# mini.net
KiCad netlist of a schematic drawn in EAGLE
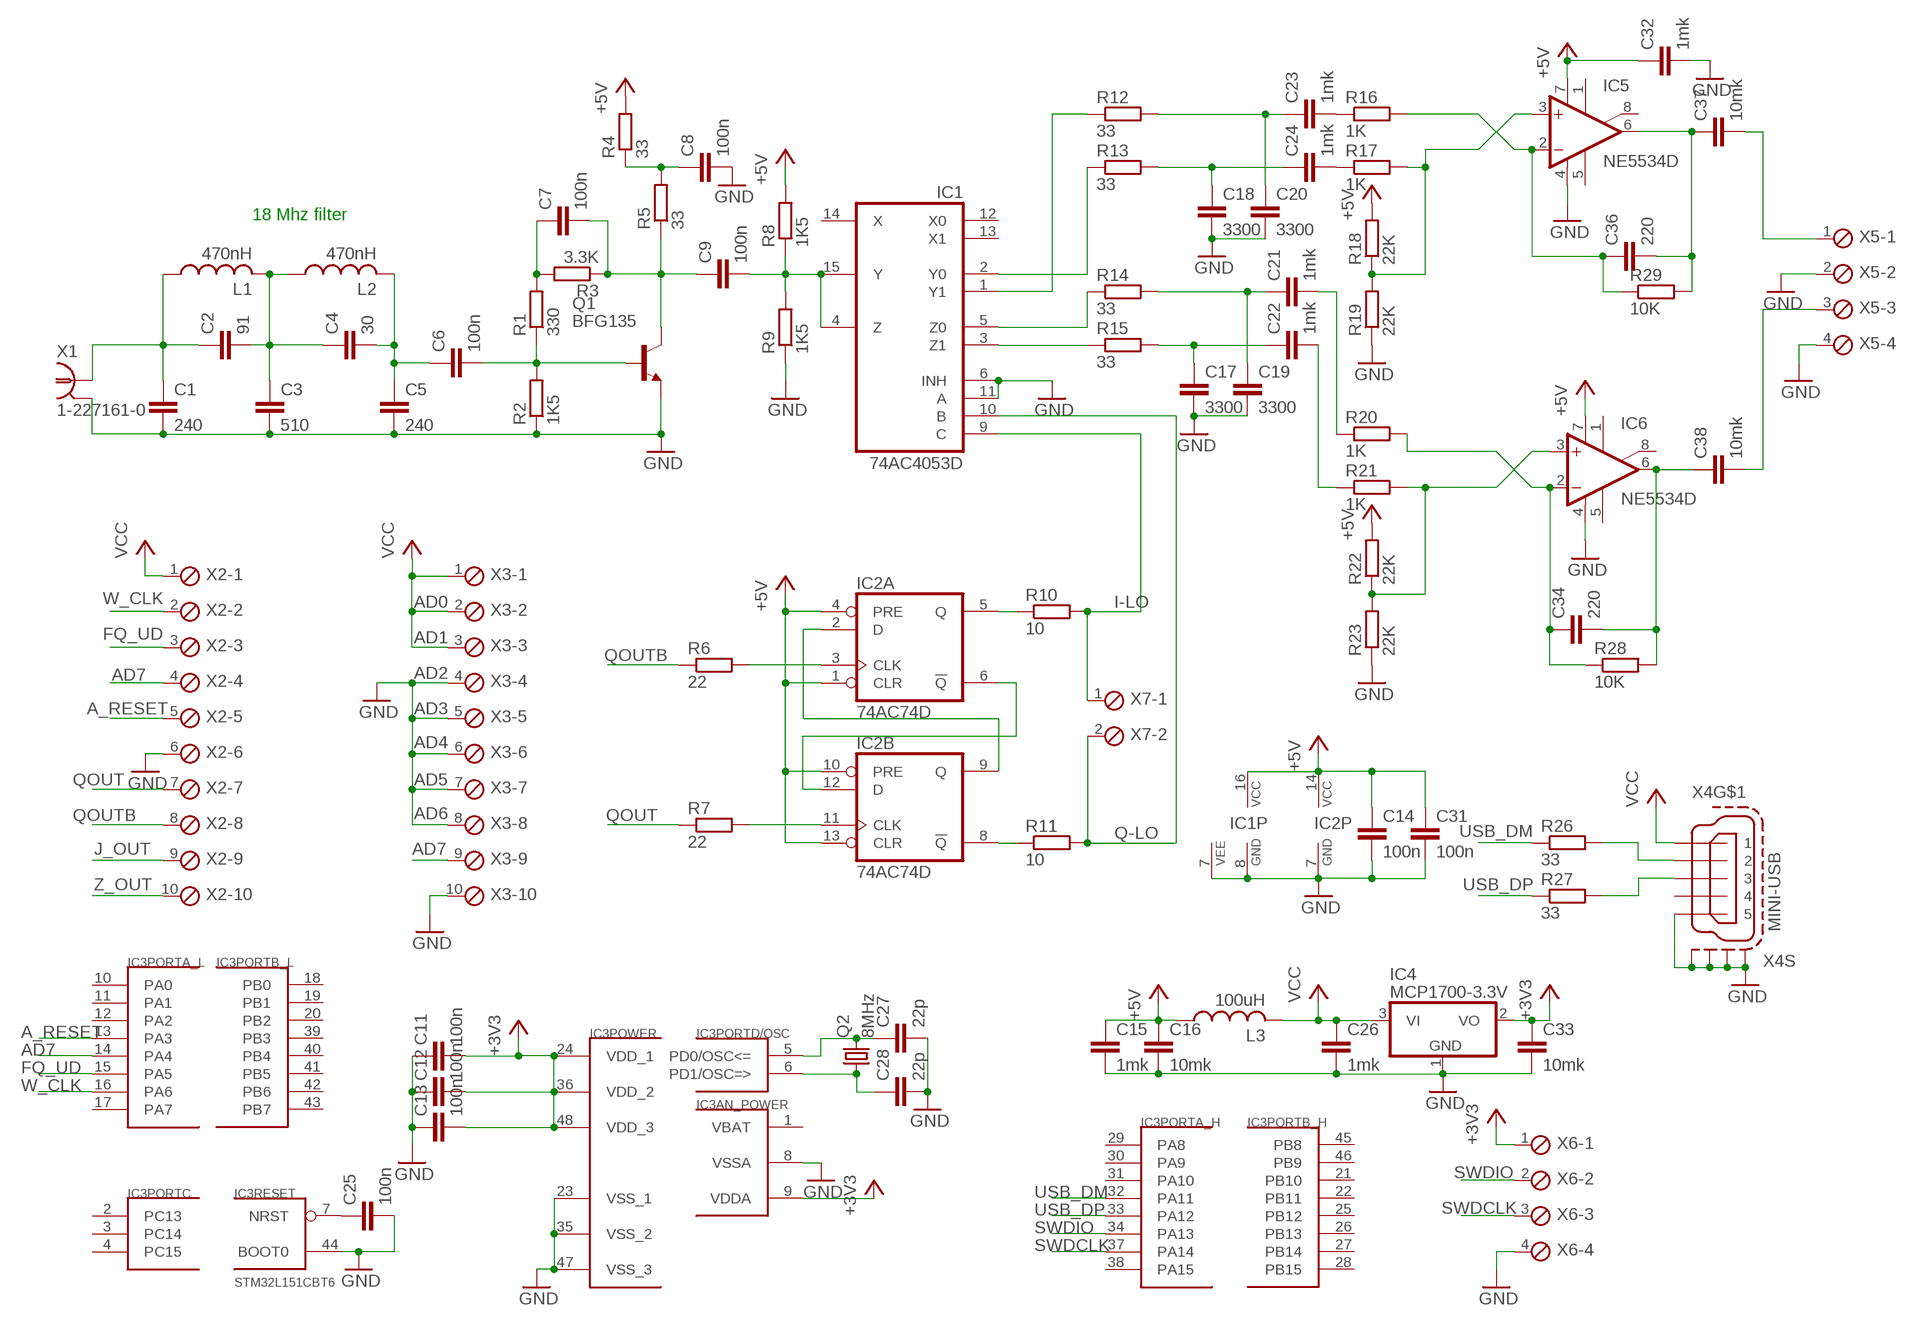
[diagram p0: schematic, sheet 1]

(export (version "E")
  (design (tool "Eeschema 10.0.6"))
  (components
    (comp (ref "C1")
      (value "240")
      (footprint "eagle-import:C0805")
      (libsource (lib "eagle-import") (part "C-EUC0805"))
    )
    (comp (ref "C2")
      (value "91")
      (footprint "eagle-import:C0805")
      (libsource (lib "eagle-import") (part "C-EUC0805"))
    )
    (comp (ref "C3")
      (value "510")
      (footprint "eagle-import:C0805")
      (libsource (lib "eagle-import") (part "C-EUC0805"))
    )
    (comp (ref "C4")
      (value "30")
      (footprint "eagle-import:C0805")
      (libsource (lib "eagle-import") (part "C-EUC0805"))
    )
    (comp (ref "C5")
      (value "240")
      (footprint "eagle-import:C0805")
      (libsource (lib "eagle-import") (part "C-EUC0805"))
    )
    (comp (ref "C6")
      (value "100n")
      (footprint "eagle-import:C0603")
      (libsource (lib "eagle-import") (part "C-EUC0603"))
    )
    (comp (ref "C7")
      (value "100n")
      (footprint "eagle-import:C0603")
      (libsource (lib "eagle-import") (part "C-EUC0603"))
    )
    (comp (ref "C8")
      (value "100n")
      (footprint "eagle-import:C0603")
      (libsource (lib "eagle-import") (part "C-EUC0603"))
    )
    (comp (ref "C9")
      (value "100n")
      (footprint "eagle-import:C0603")
      (libsource (lib "eagle-import") (part "C-EUC0603"))
    )
    (comp (ref "C11")
      (value "100n")
      (footprint "eagle-import:C0603")
      (libsource (lib "eagle-import") (part "C-EUC0603"))
    )
    (comp (ref "C12")
      (value "100n")
      (footprint "eagle-import:C0603")
      (libsource (lib "eagle-import") (part "C-EUC0603"))
    )
    (comp (ref "C13")
      (value "100n")
      (footprint "eagle-import:C0603")
      (libsource (lib "eagle-import") (part "C-EUC0603"))
    )
    (comp (ref "C14")
      (value "100n")
      (footprint "eagle-import:C0603")
      (libsource (lib "eagle-import") (part "C-EUC0603"))
    )
    (comp (ref "C15")
      (value "1mk")
      (footprint "eagle-import:C0603")
      (libsource (lib "eagle-import") (part "C-EUC0603"))
    )
    (comp (ref "C16")
      (value "10mk")
      (footprint "eagle-import:C0805")
      (libsource (lib "eagle-import") (part "C-EUC0805"))
    )
    (comp (ref "C17")
      (value "3300")
      (footprint "eagle-import:C0805")
      (libsource (lib "eagle-import") (part "C-EUC0805"))
    )
    (comp (ref "C18")
      (value "3300")
      (footprint "eagle-import:C0805")
      (libsource (lib "eagle-import") (part "C-EUC0805"))
    )
    (comp (ref "C19")
      (value "3300")
      (footprint "eagle-import:C0805")
      (libsource (lib "eagle-import") (part "C-EUC0805"))
    )
    (comp (ref "C20")
      (value "3300")
      (footprint "eagle-import:C0805")
      (libsource (lib "eagle-import") (part "C-EUC0805"))
    )
    (comp (ref "C21")
      (value "1mk")
      (footprint "eagle-import:C0603")
      (libsource (lib "eagle-import") (part "C-EUC0603"))
    )
    (comp (ref "C22")
      (value "1mk")
      (footprint "eagle-import:C0603")
      (libsource (lib "eagle-import") (part "C-EUC0603"))
    )
    (comp (ref "C23")
      (value "1mk")
      (footprint "eagle-import:C0603")
      (libsource (lib "eagle-import") (part "C-EUC0603"))
    )
    (comp (ref "C24")
      (value "1mk")
      (footprint "eagle-import:C0603")
      (libsource (lib "eagle-import") (part "C-EUC0603"))
    )
    (comp (ref "C25")
      (value "100n")
      (footprint "eagle-import:C0603")
      (libsource (lib "eagle-import") (part "C-EUC0603"))
    )
    (comp (ref "C26")
      (value "1mk")
      (footprint "eagle-import:C0603")
      (libsource (lib "eagle-import") (part "C-EUC0603"))
    )
    (comp (ref "C27")
      (value "22p")
      (footprint "eagle-import:C0603")
      (libsource (lib "eagle-import") (part "C-EUC0603"))
    )
    (comp (ref "C28")
      (value "22p")
      (footprint "eagle-import:C0603")
      (libsource (lib "eagle-import") (part "C-EUC0603"))
    )
    (comp (ref "C31")
      (value "100n")
      (footprint "eagle-import:C0603")
      (libsource (lib "eagle-import") (part "C-EUC0603"))
    )
    (comp (ref "C32")
      (value "1mk")
      (footprint "eagle-import:C0603")
      (libsource (lib "eagle-import") (part "C-EUC0603"))
    )
    (comp (ref "C33")
      (value "10mk")
      (footprint "eagle-import:C0805")
      (libsource (lib "eagle-import") (part "C-EUC0805"))
    )
    (comp (ref "C34")
      (value "220")
      (footprint "eagle-import:C0805")
      (libsource (lib "eagle-import") (part "C-EUC0805"))
    )
    (comp (ref "C36")
      (value "220")
      (footprint "eagle-import:C0805")
      (libsource (lib "eagle-import") (part "C-EUC0805"))
    )
    (comp (ref "C37")
      (value "10mk")
      (footprint "eagle-import:C0805")
      (libsource (lib "eagle-import") (part "C-EUC0805"))
    )
    (comp (ref "C38")
      (value "10mk")
      (footprint "eagle-import:C0805")
      (libsource (lib "eagle-import") (part "C-EUC0805"))
    )
    (comp (ref "IC1")
      (value "74AC4053D")
      (footprint "eagle-import:SO16")
      (libsource (lib "eagle-import") (part "4053D"))
    )
    (comp (ref "IC2")
      (value "74AC74D")
      (footprint "eagle-import:SO14")
      (libsource (lib "eagle-import") (part "7474DAC"))
    )
    (comp (ref "IC3")
      (value "STM32L151CBT6")
      (footprint "eagle-import:TQFP48")
      (libsource (lib "eagle-import") (part "STM32F10XCXT6"))
    )
    (comp (ref "IC4")
      (value "MCP1700-3.3V")
      (footprint "eagle-import:SOT23")
      (libsource (lib "eagle-import") (part "MCP1703CB"))
    )
    (comp (ref "IC5")
      (value "NE5534D")
      (footprint "eagle-import:SO08")
      (libsource (lib "eagle-import") (part "NE5534D"))
    )
    (comp (ref "IC6")
      (value "NE5534D")
      (footprint "eagle-import:SO08")
      (libsource (lib "eagle-import") (part "NE5534D"))
    )
    (comp (ref "L1")
      (value "470nH")
      (footprint "eagle-import:L3225M")
      (libsource (lib "eagle-import") (part "L-USL3225M"))
    )
    (comp (ref "L2")
      (value "470nH")
      (footprint "eagle-import:L3225M")
      (libsource (lib "eagle-import") (part "L-USL3225M"))
    )
    (comp (ref "L3")
      (value "100uH")
      (footprint "eagle-import:0207_12")
      (libsource (lib "eagle-import") (part "L-US0207/12"))
    )
    (comp (ref "Q1")
      (value "BFG135")
      (footprint "eagle-import:SOT223")
      (libsource (lib "eagle-import") (part "BFG135"))
    )
    (comp (ref "Q2")
      (value "8MHz")
      (footprint "eagle-import:HC49_S")
      (libsource (lib "eagle-import") (part "CRYSTALHC49S"))
    )
    (comp (ref "R1")
      (value "330")
      (footprint "eagle-import:R0603")
      (libsource (lib "eagle-import") (part "R-EU_R0603"))
    )
    (comp (ref "R2")
      (value "1K5")
      (footprint "eagle-import:R0603")
      (libsource (lib "eagle-import") (part "R-EU_R0603"))
    )
    (comp (ref "R3")
      (value "3.3K")
      (footprint "eagle-import:R0603")
      (libsource (lib "eagle-import") (part "R-EU_R0603"))
    )
    (comp (ref "R4")
      (value "33")
      (footprint "eagle-import:R0603")
      (libsource (lib "eagle-import") (part "R-EU_R0603"))
    )
    (comp (ref "R5")
      (value "33")
      (footprint "eagle-import:R0603")
      (libsource (lib "eagle-import") (part "R-EU_R0603"))
    )
    (comp (ref "R6")
      (value "22")
      (footprint "eagle-import:R0603")
      (libsource (lib "eagle-import") (part "R-EU_R0603"))
    )
    (comp (ref "R7")
      (value "22")
      (footprint "eagle-import:R0603")
      (libsource (lib "eagle-import") (part "R-EU_R0603"))
    )
    (comp (ref "R8")
      (value "1K5")
      (footprint "eagle-import:R0603")
      (libsource (lib "eagle-import") (part "R-EU_R0603"))
    )
    (comp (ref "R9")
      (value "1K5")
      (footprint "eagle-import:R0603")
      (libsource (lib "eagle-import") (part "R-EU_R0603"))
    )
    (comp (ref "R10")
      (value "10")
      (footprint "eagle-import:R0603")
      (libsource (lib "eagle-import") (part "R-EU_R0603"))
    )
    (comp (ref "R11")
      (value "10")
      (footprint "eagle-import:R0603")
      (libsource (lib "eagle-import") (part "R-EU_R0603"))
    )
    (comp (ref "R12")
      (value "33")
      (footprint "eagle-import:R0603")
      (libsource (lib "eagle-import") (part "R-EU_R0603"))
    )
    (comp (ref "R13")
      (value "33")
      (footprint "eagle-import:R0603")
      (libsource (lib "eagle-import") (part "R-EU_R0603"))
    )
    (comp (ref "R14")
      (value "33")
      (footprint "eagle-import:R0603")
      (libsource (lib "eagle-import") (part "R-EU_R0603"))
    )
    (comp (ref "R15")
      (value "33")
      (footprint "eagle-import:R0603")
      (libsource (lib "eagle-import") (part "R-EU_R0603"))
    )
    (comp (ref "R16")
      (value "1K")
      (footprint "eagle-import:R0603")
      (libsource (lib "eagle-import") (part "R-EU_R0603"))
    )
    (comp (ref "R17")
      (value "1K")
      (footprint "eagle-import:R0603")
      (libsource (lib "eagle-import") (part "R-EU_R0603"))
    )
    (comp (ref "R18")
      (value "22K")
      (footprint "eagle-import:R0603")
      (libsource (lib "eagle-import") (part "R-EU_R0603"))
    )
    (comp (ref "R19")
      (value "22K")
      (footprint "eagle-import:R0603")
      (libsource (lib "eagle-import") (part "R-EU_R0603"))
    )
    (comp (ref "R20")
      (value "1K")
      (footprint "eagle-import:R0603")
      (libsource (lib "eagle-import") (part "R-EU_R0603"))
    )
    (comp (ref "R21")
      (value "1K")
      (footprint "eagle-import:R0603")
      (libsource (lib "eagle-import") (part "R-EU_R0603"))
    )
    (comp (ref "R22")
      (value "22K")
      (footprint "eagle-import:R0603")
      (libsource (lib "eagle-import") (part "R-EU_R0603"))
    )
    (comp (ref "R23")
      (value "22K")
      (footprint "eagle-import:R0603")
      (libsource (lib "eagle-import") (part "R-EU_R0603"))
    )
    (comp (ref "R26")
      (value "33")
      (footprint "eagle-import:R0603")
      (libsource (lib "eagle-import") (part "R-EU_R0603"))
    )
    (comp (ref "R27")
      (value "33")
      (footprint "eagle-import:R0603")
      (libsource (lib "eagle-import") (part "R-EU_R0603"))
    )
    (comp (ref "R28")
      (value "10K")
      (footprint "eagle-import:R0603")
      (libsource (lib "eagle-import") (part "R-EU_R0603"))
    )
    (comp (ref "R29")
      (value "10K")
      (footprint "eagle-import:R0603")
      (libsource (lib "eagle-import") (part "R-EU_R0603"))
    )
    (comp (ref "X1")
      (value "1-227161-0")
      (footprint "eagle-import:AMP_227161")
      (fields (field (name "MF") "TYCO ELECTRONICS") (field (name "MPN") "1-227161"))
      (libsource (lib "eagle-import") (part "?2271611--0"))
    )
    (comp (ref "X2")
      (value "MPT10")
      (footprint "eagle-import:10POL254")
      (libsource (lib "eagle-import") (part "MPT10"))
    )
    (comp (ref "X3")
      (value "MPT10")
      (footprint "eagle-import:10POL254")
      (libsource (lib "eagle-import") (part "MPT10"))
    )
    (comp (ref "X4")
      (value "MINI-USB")
      (footprint "eagle-import:32005-301")
      (libsource (lib "eagle-import") (part "MINI-USB-SCHIELD-32005-301"))
    )
    (comp (ref "X5")
      (value "MPT4")
      (footprint "eagle-import:4POL254")
      (libsource (lib "eagle-import") (part "MPT4"))
    )
    (comp (ref "X6")
      (value "MPT4")
      (footprint "eagle-import:4POL254")
      (libsource (lib "eagle-import") (part "MPT4"))
    )
    (comp (ref "X7")
      (value "MPT2")
      (footprint "eagle-import:2POL254")
      (libsource (lib "eagle-import") (part "MPT2"))
    )
  )
  (nets
    (net (code "1") (name "+3V3") (class "Default")
      (node (ref "C11") (pin "2") (pinfunction "2_2") (pintype "passive"))
      (node (ref "C12") (pin "2") (pinfunction "2_2") (pintype "passive"))
      (node (ref "C13") (pin "2") (pinfunction "2_2") (pintype "passive"))
      (node (ref "C33") (pin "1") (pinfunction "1_1") (pintype "passive"))
      (node (ref "IC3") (pin "24") (pinfunction "VDD_1_24") (pintype "power_in"))
      (node (ref "IC3") (pin "36") (pinfunction "VDD_2_36") (pintype "power_in"))
      (node (ref "IC3") (pin "48") (pinfunction "VDD_3_48") (pintype "power_in"))
      (node (ref "IC3") (pin "9") (pinfunction "VDDA_9") (pintype "power_in"))
      (node (ref "IC4") (pin "2") (pinfunction "VO_2") (pintype "passive"))
      (node (ref "X6") (pin "1") (pinfunction "1_1") (pintype "passive"))
    )
    (net (code "2") (name "+5V") (class "Default")
      (node (ref "C14") (pin "1") (pinfunction "1_1") (pintype "passive"))
      (node (ref "C15") (pin "1") (pinfunction "1_1") (pintype "passive"))
      (node (ref "C16") (pin "1") (pinfunction "1_1") (pintype "passive"))
      (node (ref "C31") (pin "1") (pinfunction "1_1") (pintype "passive"))
      (node (ref "C32") (pin "1") (pinfunction "1_1") (pintype "passive"))
      (node (ref "IC1") (pin "16") (pinfunction "VCC_16") (pintype "power_in"))
      (node (ref "IC2") (pin "1") (pinfunction "CLR_1") (pintype "input"))
      (node (ref "IC2") (pin "10") (pinfunction "PRE_10") (pintype "input"))
      (node (ref "IC2") (pin "13") (pinfunction "CLR_13") (pintype "input"))
      (node (ref "IC2") (pin "14") (pinfunction "VCC_14") (pintype "power_in"))
      (node (ref "IC2") (pin "4") (pinfunction "PRE_4") (pintype "input"))
      (node (ref "IC5") (pin "7") (pinfunction "V+_7") (pintype "power_in"))
      (node (ref "IC6") (pin "7") (pinfunction "V+_7") (pintype "power_in"))
      (node (ref "L3") (pin "1") (pinfunction "1_1") (pintype "passive"))
      (node (ref "R18") (pin "2") (pinfunction "2_2") (pintype "passive"))
      (node (ref "R22") (pin "2") (pinfunction "2_2") (pintype "passive"))
      (node (ref "R4") (pin "2") (pinfunction "2_2") (pintype "passive"))
      (node (ref "R8") (pin "2") (pinfunction "2_2") (pintype "passive"))
    )
    (net (code "3") (name "/AD7") (class "Default")
      (node (ref "IC3") (pin "14") (pinfunction "PA4_14") (pintype "bidirectional"))
      (node (ref "X2") (pin "4") (pinfunction "1_4") (pintype "passive"))
    )
    (net (code "4") (name "/A_RESET") (class "Default")
      (node (ref "IC3") (pin "13") (pinfunction "PA3_13") (pintype "bidirectional"))
      (node (ref "X2") (pin "5") (pinfunction "1_5") (pintype "passive"))
    )
    (net (code "5") (name "/FQ_UD") (class "Default")
      (node (ref "IC3") (pin "15") (pinfunction "PA5_15") (pintype "bidirectional"))
      (node (ref "X2") (pin "3") (pinfunction "1_3") (pintype "passive"))
    )
    (net (code "6") (name "/I-LO") (class "Default")
      (node (ref "IC1") (pin "9") (pinfunction "C_9") (pintype "input"))
      (node (ref "R10") (pin "2") (pinfunction "2_2") (pintype "passive"))
      (node (ref "X7") (pin "1") (pinfunction "1_1") (pintype "passive"))
    )
    (net (code "7") (name "/J_OUT") (class "Default")
      (node (ref "X2") (pin "9") (pinfunction "1_9") (pintype "passive"))
    )
    (net (code "8") (name "/Q-LO") (class "Default")
      (node (ref "IC1") (pin "10") (pinfunction "B_10") (pintype "input"))
      (node (ref "R11") (pin "2") (pinfunction "2_2") (pintype "passive"))
      (node (ref "X7") (pin "2") (pinfunction "1_2") (pintype "passive"))
    )
    (net (code "9") (name "/QOUT") (class "Default")
      (node (ref "R7") (pin "1") (pinfunction "1_1") (pintype "passive"))
      (node (ref "X2") (pin "7") (pinfunction "1_7") (pintype "passive"))
    )
    (net (code "10") (name "/QOUTB") (class "Default")
      (node (ref "R6") (pin "1") (pinfunction "1_1") (pintype "passive"))
      (node (ref "X2") (pin "8") (pinfunction "1_8") (pintype "passive"))
    )
    (net (code "11") (name "/SWDCLK") (class "Default")
      (node (ref "IC3") (pin "37") (pinfunction "PA14_37") (pintype "bidirectional"))
      (node (ref "X6") (pin "3") (pinfunction "1_3") (pintype "passive"))
    )
    (net (code "12") (name "/SWDIO") (class "Default")
      (node (ref "IC3") (pin "34") (pinfunction "PA13_34") (pintype "bidirectional"))
      (node (ref "X6") (pin "2") (pinfunction "1_2") (pintype "passive"))
    )
    (net (code "13") (name "/USB_DM") (class "Default")
      (node (ref "IC3") (pin "32") (pinfunction "PA11_32") (pintype "bidirectional"))
      (node (ref "R26") (pin "1") (pinfunction "1_1") (pintype "passive"))
    )
    (net (code "14") (name "/USB_DP") (class "Default")
      (node (ref "IC3") (pin "33") (pinfunction "PA12_33") (pintype "bidirectional"))
      (node (ref "R27") (pin "1") (pinfunction "1_1") (pintype "passive"))
    )
    (net (code "15") (name "/VBAT") (class "Default")
      (node (ref "IC3") (pin "1") (pinfunction "VBAT_1") (pintype "power_in"))
    )
    (net (code "16") (name "/W_CLK") (class "Default")
      (node (ref "IC3") (pin "16") (pinfunction "PA6_16") (pintype "bidirectional"))
      (node (ref "X2") (pin "2") (pinfunction "1_2") (pintype "passive"))
    )
    (net (code "17") (name "/Z_OUT") (class "Default")
      (node (ref "X2") (pin "10") (pinfunction "1_10") (pintype "passive"))
    )
    (net (code "18") (name "GND") (class "Default")
      (node (ref "C1") (pin "2") (pinfunction "2_2") (pintype "passive"))
      (node (ref "C11") (pin "1") (pinfunction "1_1") (pintype "passive"))
      (node (ref "C12") (pin "1") (pinfunction "1_1") (pintype "passive"))
      (node (ref "C13") (pin "1") (pinfunction "1_1") (pintype "passive"))
      (node (ref "C14") (pin "2") (pinfunction "2_2") (pintype "passive"))
      (node (ref "C15") (pin "2") (pinfunction "2_2") (pintype "passive"))
      (node (ref "C16") (pin "2") (pinfunction "2_2") (pintype "passive"))
      (node (ref "C17") (pin "2") (pinfunction "2_2") (pintype "passive"))
      (node (ref "C18") (pin "2") (pinfunction "2_2") (pintype "passive"))
      (node (ref "C19") (pin "2") (pinfunction "2_2") (pintype "passive"))
      (node (ref "C20") (pin "2") (pinfunction "2_2") (pintype "passive"))
      (node (ref "C25") (pin "2") (pinfunction "2_2") (pintype "passive"))
      (node (ref "C26") (pin "2") (pinfunction "2_2") (pintype "passive"))
      (node (ref "C27") (pin "2") (pinfunction "2_2") (pintype "passive"))
      (node (ref "C28") (pin "2") (pinfunction "2_2") (pintype "passive"))
      (node (ref "C3") (pin "2") (pinfunction "2_2") (pintype "passive"))
      (node (ref "C31") (pin "2") (pinfunction "2_2") (pintype "passive"))
      (node (ref "C32") (pin "2") (pinfunction "2_2") (pintype "passive"))
      (node (ref "C33") (pin "2") (pinfunction "2_2") (pintype "passive"))
      (node (ref "C5") (pin "2") (pinfunction "2_2") (pintype "passive"))
      (node (ref "C8") (pin "2") (pinfunction "2_2") (pintype "passive"))
      (node (ref "IC1") (pin "11") (pinfunction "A_11") (pintype "input"))
      (node (ref "IC1") (pin "6") (pinfunction "INH_6") (pintype "input"))
      (node (ref "IC1") (pin "7") (pinfunction "VEE_7") (pintype "power_in"))
      (node (ref "IC1") (pin "8") (pinfunction "GND_8") (pintype "power_in"))
      (node (ref "IC2") (pin "7") (pinfunction "GND_7") (pintype "power_in"))
      (node (ref "IC3") (pin "23") (pinfunction "VSS_1_23") (pintype "power_in"))
      (node (ref "IC3") (pin "35") (pinfunction "VSS_2_35") (pintype "power_in"))
      (node (ref "IC3") (pin "44") (pinfunction "BOOT0_44") (pintype "input"))
      (node (ref "IC3") (pin "47") (pinfunction "VSS_3_47") (pintype "power_in"))
      (node (ref "IC3") (pin "8") (pinfunction "VSSA_8") (pintype "power_in"))
      (node (ref "IC4") (pin "1") (pinfunction "GND_1") (pintype "passive"))
      (node (ref "IC5") (pin "4") (pinfunction "V-_4") (pintype "power_in"))
      (node (ref "IC6") (pin "4") (pinfunction "V-_4") (pintype "power_in"))
      (node (ref "Q1") (pin "1") (pinfunction "E_1") (pintype "passive"))
      (node (ref "Q1") (pin "3") (pinfunction "E_3") (pintype "passive"))
      (node (ref "R19") (pin "1") (pinfunction "1_1") (pintype "passive"))
      (node (ref "R2") (pin "1") (pinfunction "1_1") (pintype "passive"))
      (node (ref "R23") (pin "1") (pinfunction "1_1") (pintype "passive"))
      (node (ref "R9") (pin "1") (pinfunction "1_1") (pintype "passive"))
      (node (ref "X1") (pin "2") (pinfunction "2_2") (pintype "passive"))
      (node (ref "X2") (pin "6") (pinfunction "1_6") (pintype "passive"))
      (node (ref "X3") (pin "10") (pinfunction "1_10") (pintype "passive"))
      (node (ref "X3") (pin "4") (pinfunction "1_4") (pintype "passive"))
      (node (ref "X3") (pin "5") (pinfunction "1_5") (pintype "passive"))
      (node (ref "X3") (pin "6") (pinfunction "1_6") (pintype "passive"))
      (node (ref "X3") (pin "7") (pinfunction "1_7") (pintype "passive"))
      (node (ref "X3") (pin "8") (pinfunction "1_8") (pintype "passive"))
      (node (ref "X4") (pin "5") (pinfunction "5_5") (pintype "passive"))
      (node (ref "X4") (pin "M1") (pinfunction "S1_M1") (pintype "passive"))
      (node (ref "X4") (pin "M2") (pinfunction "S2_M2") (pintype "passive"))
      (node (ref "X4") (pin "M3") (pinfunction "S3_M3") (pintype "passive"))
      (node (ref "X4") (pin "M4") (pinfunction "S4_M4") (pintype "passive"))
      (node (ref "X5") (pin "2") (pinfunction "1_2") (pintype "passive"))
      (node (ref "X5") (pin "4") (pinfunction "1_4") (pintype "passive"))
      (node (ref "X6") (pin "4") (pinfunction "1_4") (pintype "passive"))
    )
    (net (code "19") (name "Net-(C1-Pad1)") (class "Default")
      (node (ref "C1") (pin "1") (pinfunction "1_1") (pintype "passive"))
      (node (ref "C2") (pin "1") (pinfunction "1_1") (pintype "passive"))
      (node (ref "L1") (pin "1") (pinfunction "1_1") (pintype "passive"))
      (node (ref "X1") (pin "1") (pinfunction "1_1") (pintype "passive"))
    )
    (net (code "20") (name "Net-(C2-Pad2)") (class "Default")
      (node (ref "C2") (pin "2") (pinfunction "2_2") (pintype "passive"))
      (node (ref "C3") (pin "1") (pinfunction "1_1") (pintype "passive"))
      (node (ref "C4") (pin "1") (pinfunction "1_1") (pintype "passive"))
      (node (ref "L1") (pin "2") (pinfunction "2_2") (pintype "passive"))
      (node (ref "L2") (pin "1") (pinfunction "1_1") (pintype "passive"))
    )
    (net (code "21") (name "Net-(C4-Pad2)") (class "Default")
      (node (ref "C4") (pin "2") (pinfunction "2_2") (pintype "passive"))
      (node (ref "C5") (pin "1") (pinfunction "1_1") (pintype "passive"))
      (node (ref "C6") (pin "1") (pinfunction "1_1") (pintype "passive"))
      (node (ref "L2") (pin "2") (pinfunction "2_2") (pintype "passive"))
    )
    (net (code "22") (name "Net-(C7-Pad1)") (class "Default")
      (node (ref "C7") (pin "1") (pinfunction "1_1") (pintype "passive"))
      (node (ref "R1") (pin "2") (pinfunction "2_2") (pintype "passive"))
      (node (ref "R3") (pin "2") (pinfunction "2_2") (pintype "passive"))
    )
    (net (code "23") (name "Net-(C8-Pad1)") (class "Default")
      (node (ref "C8") (pin "1") (pinfunction "1_1") (pintype "passive"))
      (node (ref "R4") (pin "1") (pinfunction "1_1") (pintype "passive"))
      (node (ref "R5") (pin "2") (pinfunction "2_2") (pintype "passive"))
    )
    (net (code "24") (name "Net-(C17-Pad1)") (class "Default")
      (node (ref "C17") (pin "1") (pinfunction "1_1") (pintype "passive"))
      (node (ref "C22") (pin "1") (pinfunction "1_1") (pintype "passive"))
      (node (ref "R15") (pin "2") (pinfunction "2_2") (pintype "passive"))
    )
    (net (code "25") (name "Net-(C18-Pad1)") (class "Default")
      (node (ref "C18") (pin "1") (pinfunction "1_1") (pintype "passive"))
      (node (ref "C24") (pin "1") (pinfunction "1_1") (pintype "passive"))
      (node (ref "R13") (pin "2") (pinfunction "2_2") (pintype "passive"))
    )
    (net (code "26") (name "Net-(C19-Pad1)") (class "Default")
      (node (ref "C19") (pin "1") (pinfunction "1_1") (pintype "passive"))
      (node (ref "C21") (pin "1") (pinfunction "1_1") (pintype "passive"))
      (node (ref "R14") (pin "2") (pinfunction "2_2") (pintype "passive"))
    )
    (net (code "27") (name "Net-(C20-Pad1)") (class "Default")
      (node (ref "C20") (pin "1") (pinfunction "1_1") (pintype "passive"))
      (node (ref "C23") (pin "1") (pinfunction "1_1") (pintype "passive"))
      (node (ref "R12") (pin "2") (pinfunction "2_2") (pintype "passive"))
    )
    (net (code "28") (name "Net-(C21-Pad2)") (class "Default")
      (node (ref "C21") (pin "2") (pinfunction "2_2") (pintype "passive"))
      (node (ref "R20") (pin "1") (pinfunction "1_1") (pintype "passive"))
    )
    (net (code "29") (name "Net-(C22-Pad2)") (class "Default")
      (node (ref "C22") (pin "2") (pinfunction "2_2") (pintype "passive"))
      (node (ref "R21") (pin "1") (pinfunction "1_1") (pintype "passive"))
    )
    (net (code "30") (name "Net-(C23-Pad2)") (class "Default")
      (node (ref "C23") (pin "2") (pinfunction "2_2") (pintype "passive"))
      (node (ref "R16") (pin "1") (pinfunction "1_1") (pintype "passive"))
    )
    (net (code "31") (name "Net-(C24-Pad2)") (class "Default")
      (node (ref "C24") (pin "2") (pinfunction "2_2") (pintype "passive"))
      (node (ref "R17") (pin "1") (pinfunction "1_1") (pintype "passive"))
    )
    (net (code "32") (name "Net-(C37-Pad2)") (class "Default")
      (node (ref "C37") (pin "2") (pinfunction "2_2") (pintype "passive"))
      (node (ref "X5") (pin "1") (pinfunction "1_1") (pintype "passive"))
    )
    (net (code "33") (name "Net-(IC1A-Y)") (class "Default")
      (node (ref "C9") (pin "2") (pinfunction "2_2") (pintype "passive"))
      (node (ref "IC1") (pin "15") (pinfunction "Y_15") (pintype "bidirectional"))
      (node (ref "IC1") (pin "4") (pinfunction "Z_4") (pintype "bidirectional"))
      (node (ref "R8") (pin "1") (pinfunction "1_1") (pintype "passive"))
      (node (ref "R9") (pin "2") (pinfunction "2_2") (pintype "passive"))
    )
    (net (code "34") (name "Net-(IC1A-Y0)") (class "Default")
      (node (ref "IC1") (pin "2") (pinfunction "Y0_2") (pintype "bidirectional"))
      (node (ref "R13") (pin "1") (pinfunction "1_1") (pintype "passive"))
    )
    (net (code "35") (name "Net-(IC1A-Y1)") (class "Default")
      (node (ref "IC1") (pin "1") (pinfunction "Y1_1") (pintype "bidirectional"))
      (node (ref "R12") (pin "1") (pinfunction "1_1") (pintype "passive"))
    )
    (net (code "36") (name "Net-(IC1A-Z0)") (class "Default")
      (node (ref "IC1") (pin "5") (pinfunction "Z0_5") (pintype "bidirectional"))
      (node (ref "R14") (pin "1") (pinfunction "1_1") (pintype "passive"))
    )
    (net (code "37") (name "Net-(IC1A-Z1)") (class "Default")
      (node (ref "IC1") (pin "3") (pinfunction "Z1_3") (pintype "bidirectional"))
      (node (ref "R15") (pin "1") (pinfunction "1_1") (pintype "passive"))
    )
    (net (code "38") (name "Net-(IC2A-CLK)") (class "Default")
      (node (ref "IC2") (pin "3") (pinfunction "CLK_3") (pintype "input"))
      (node (ref "R6") (pin "2") (pinfunction "2_2") (pintype "passive"))
    )
    (net (code "39") (name "Net-(IC2A-D)") (class "Default")
      (node (ref "IC2") (pin "2") (pinfunction "D_2") (pintype "input"))
      (node (ref "IC2") (pin "9") (pinfunction "Q_9") (pintype "output"))
    )
    (net (code "40") (name "Net-(IC2A-Q)") (class "Default")
      (node (ref "IC2") (pin "5") (pinfunction "Q_5") (pintype "output"))
      (node (ref "R10") (pin "1") (pinfunction "1_1") (pintype "passive"))
    )
    (net (code "41") (name "Net-(IC2A-~{Q})") (class "Default")
      (node (ref "IC2") (pin "12") (pinfunction "D_12") (pintype "input"))
      (node (ref "IC2") (pin "6") (pinfunction "~{Q}_6") (pintype "output"))
    )
    (net (code "42") (name "Net-(IC2B-CLK)") (class "Default")
      (node (ref "IC2") (pin "11") (pinfunction "CLK_11") (pintype "input"))
      (node (ref "R7") (pin "2") (pinfunction "2_2") (pintype "passive"))
    )
    (net (code "43") (name "Net-(IC2B-~{Q})") (class "Default")
      (node (ref "IC2") (pin "8") (pinfunction "~{Q}_8") (pintype "output"))
      (node (ref "R11") (pin "1") (pinfunction "1_1") (pintype "passive"))
    )
    (net (code "44") (name "Net-(IC3G-PD0{slash}OSC<=)") (class "Default")
      (node (ref "C27") (pin "1") (pinfunction "1_1") (pintype "passive"))
      (node (ref "IC3") (pin "5") (pinfunction "PD0/OSC<=_5") (pintype "bidirectional"))
      (node (ref "Q2") (pin "2") (pinfunction "2_2") (pintype "passive"))
    )
    (net (code "45") (name "Net-(IC3G-PD1{slash}OSC=>)") (class "Default")
      (node (ref "C28") (pin "1") (pinfunction "1_1") (pintype "passive"))
      (node (ref "IC3") (pin "6") (pinfunction "PD1/OSC=>_6") (pintype "bidirectional"))
      (node (ref "Q2") (pin "1") (pinfunction "1_1") (pintype "passive"))
    )
    (net (code "46") (name "Net-(IC3I-NRST)") (class "Default")
      (node (ref "C25") (pin "1") (pinfunction "1_1") (pintype "passive"))
      (node (ref "IC3") (pin "7") (pinfunction "NRST_7") (pintype "input"))
    )
    (net (code "47") (name "Net-(IC5-+IN)") (class "Default")
      (node (ref "IC5") (pin "3") (pinfunction "+IN_3") (pintype "input"))
      (node (ref "R17") (pin "2") (pinfunction "2_2") (pintype "passive"))
      (node (ref "R18") (pin "1") (pinfunction "1_1") (pintype "passive"))
      (node (ref "R19") (pin "2") (pinfunction "2_2") (pintype "passive"))
    )
    (net (code "48") (name "Net-(IC5--IN)") (class "Default")
      (node (ref "C36") (pin "1") (pinfunction "1_1") (pintype "passive"))
      (node (ref "IC5") (pin "2") (pinfunction "-IN_2") (pintype "input"))
      (node (ref "R16") (pin "2") (pinfunction "2_2") (pintype "passive"))
      (node (ref "R29") (pin "1") (pinfunction "1_1") (pintype "passive"))
    )
    (net (code "49") (name "Net-(IC5-OUT)") (class "Default")
      (node (ref "C36") (pin "2") (pinfunction "2_2") (pintype "passive"))
      (node (ref "C37") (pin "1") (pinfunction "1_1") (pintype "passive"))
      (node (ref "IC5") (pin "6") (pinfunction "OUT_6") (pintype "output"))
      (node (ref "R29") (pin "2") (pinfunction "2_2") (pintype "passive"))
    )
    (net (code "50") (name "Net-(IC6-+IN)") (class "Default")
      (node (ref "IC6") (pin "3") (pinfunction "+IN_3") (pintype "input"))
      (node (ref "R21") (pin "2") (pinfunction "2_2") (pintype "passive"))
      (node (ref "R22") (pin "1") (pinfunction "1_1") (pintype "passive"))
      (node (ref "R23") (pin "2") (pinfunction "2_2") (pintype "passive"))
    )
    (net (code "51") (name "Net-(IC6--IN)") (class "Default")
      (node (ref "C34") (pin "1") (pinfunction "1_1") (pintype "passive"))
      (node (ref "IC6") (pin "2") (pinfunction "-IN_2") (pintype "input"))
      (node (ref "R20") (pin "2") (pinfunction "2_2") (pintype "passive"))
      (node (ref "R28") (pin "1") (pinfunction "1_1") (pintype "passive"))
    )
    (net (code "52") (name "Net-(IC6-OUT)") (class "Default")
      (node (ref "C34") (pin "2") (pinfunction "2_2") (pintype "passive"))
      (node (ref "C38") (pin "1") (pinfunction "1_1") (pintype "passive"))
      (node (ref "IC6") (pin "6") (pinfunction "OUT_6") (pintype "output"))
      (node (ref "R28") (pin "2") (pinfunction "2_2") (pintype "passive"))
    )
    (net (code "53") (name "Net-(Q1-B)") (class "Default")
      (node (ref "C6") (pin "2") (pinfunction "2_2") (pintype "passive"))
      (node (ref "Q1") (pin "2") (pinfunction "B_2") (pintype "passive"))
      (node (ref "R1") (pin "1") (pinfunction "1_1") (pintype "passive"))
      (node (ref "R2") (pin "2") (pinfunction "2_2") (pintype "passive"))
    )
    (net (code "54") (name "Net-(Q1-C)") (class "Default")
      (node (ref "C7") (pin "2") (pinfunction "2_2") (pintype "passive"))
      (node (ref "C9") (pin "1") (pinfunction "1_1") (pintype "passive"))
      (node (ref "Q1") (pin "4") (pinfunction "C_4") (pintype "passive"))
      (node (ref "R3") (pin "1") (pinfunction "1_1") (pintype "passive"))
      (node (ref "R5") (pin "1") (pinfunction "1_1") (pintype "passive"))
    )
    (net (code "55") (name "Net-(R26-Pad2)") (class "Default")
      (node (ref "R26") (pin "2") (pinfunction "2_2") (pintype "passive"))
      (node (ref "X4") (pin "2") (pinfunction "2_2") (pintype "passive"))
    )
    (net (code "56") (name "Net-(R27-Pad2)") (class "Default")
      (node (ref "R27") (pin "2") (pinfunction "2_2") (pintype "passive"))
      (node (ref "X4") (pin "3") (pinfunction "3_3") (pintype "passive"))
    )
    (net (code "57") (name "Net-(X5C-1)") (class "Default")
      (node (ref "C38") (pin "2") (pinfunction "2_2") (pintype "passive"))
      (node (ref "X5") (pin "3") (pinfunction "1_3") (pintype "passive"))
    )
    (net (code "58") (name "VCC") (class "Default")
      (node (ref "C26") (pin "1") (pinfunction "1_1") (pintype "passive"))
      (node (ref "IC4") (pin "3") (pinfunction "VI_3") (pintype "input"))
      (node (ref "L3") (pin "2") (pinfunction "2_2") (pintype "passive"))
      (node (ref "X2") (pin "1") (pinfunction "1_1") (pintype "passive"))
      (node (ref "X3") (pin "1") (pinfunction "1_1") (pintype "passive"))
      (node (ref "X3") (pin "2") (pinfunction "1_2") (pintype "passive"))
      (node (ref "X3") (pin "3") (pinfunction "1_3") (pintype "passive"))
      (node (ref "X4") (pin "1") (pinfunction "1_1") (pintype "passive"))
    )
    (net (code "59") (name "unconnected-(IC1A-X-Pad14)") (class "Default")
      (node (ref "IC1") (pin "14") (pinfunction "X_14") (pintype "bidirectional"))
    )
    (net (code "60") (name "unconnected-(IC1A-X0-Pad12)") (class "Default")
      (node (ref "IC1") (pin "12") (pinfunction "X0_12") (pintype "bidirectional"))
    )
    (net (code "61") (name "unconnected-(IC1A-X1-Pad13)") (class "Default")
      (node (ref "IC1") (pin "13") (pinfunction "X1_13") (pintype "bidirectional"))
    )
    (net (code "62") (name "unconnected-(IC3B-PA8-Pad29)") (class "Default")
      (node (ref "IC3") (pin "29") (pinfunction "PA8_29") (pintype "bidirectional"))
    )
    (net (code "63") (name "unconnected-(IC3B-PA9-Pad30)") (class "Default")
      (node (ref "IC3") (pin "30") (pinfunction "PA9_30") (pintype "bidirectional"))
    )
    (net (code "64") (name "unconnected-(IC3B-PA10-Pad31)") (class "Default")
      (node (ref "IC3") (pin "31") (pinfunction "PA10_31") (pintype "bidirectional"))
    )
    (net (code "65") (name "unconnected-(IC3B-PA15-Pad38)") (class "Default")
      (node (ref "IC3") (pin "38") (pinfunction "PA15_38") (pintype "bidirectional"))
    )
    (net (code "66") (name "unconnected-(IC3C-PA0-Pad10)") (class "Default")
      (node (ref "IC3") (pin "10") (pinfunction "PA0_10") (pintype "bidirectional"))
    )
    (net (code "67") (name "unconnected-(IC3C-PA1-Pad11)") (class "Default")
      (node (ref "IC3") (pin "11") (pinfunction "PA1_11") (pintype "bidirectional"))
    )
    (net (code "68") (name "unconnected-(IC3C-PA2-Pad12)") (class "Default")
      (node (ref "IC3") (pin "12") (pinfunction "PA2_12") (pintype "bidirectional"))
    )
    (net (code "69") (name "unconnected-(IC3C-PA7-Pad17)") (class "Default")
      (node (ref "IC3") (pin "17") (pinfunction "PA7_17") (pintype "bidirectional"))
    )
    (net (code "70") (name "unconnected-(IC3D-PB8-Pad45)") (class "Default")
      (node (ref "IC3") (pin "45") (pinfunction "PB8_45") (pintype "bidirectional"))
    )
    (net (code "71") (name "unconnected-(IC3D-PB9-Pad46)") (class "Default")
      (node (ref "IC3") (pin "46") (pinfunction "PB9_46") (pintype "bidirectional"))
    )
    (net (code "72") (name "unconnected-(IC3D-PB10-Pad21)") (class "Default")
      (node (ref "IC3") (pin "21") (pinfunction "PB10_21") (pintype "bidirectional"))
    )
    (net (code "73") (name "unconnected-(IC3D-PB11-Pad22)") (class "Default")
      (node (ref "IC3") (pin "22") (pinfunction "PB11_22") (pintype "bidirectional"))
    )
    (net (code "74") (name "unconnected-(IC3D-PB12-Pad25)") (class "Default")
      (node (ref "IC3") (pin "25") (pinfunction "PB12_25") (pintype "bidirectional"))
    )
    (net (code "75") (name "unconnected-(IC3D-PB13-Pad26)") (class "Default")
      (node (ref "IC3") (pin "26") (pinfunction "PB13_26") (pintype "bidirectional"))
    )
    (net (code "76") (name "unconnected-(IC3D-PB14-Pad27)") (class "Default")
      (node (ref "IC3") (pin "27") (pinfunction "PB14_27") (pintype "bidirectional"))
    )
    (net (code "77") (name "unconnected-(IC3D-PB15-Pad28)") (class "Default")
      (node (ref "IC3") (pin "28") (pinfunction "PB15_28") (pintype "bidirectional"))
    )
    (net (code "78") (name "unconnected-(IC3E-PB0-Pad18)") (class "Default")
      (node (ref "IC3") (pin "18") (pinfunction "PB0_18") (pintype "bidirectional"))
    )
    (net (code "79") (name "unconnected-(IC3E-PB1-Pad19)") (class "Default")
      (node (ref "IC3") (pin "19") (pinfunction "PB1_19") (pintype "bidirectional"))
    )
    (net (code "80") (name "unconnected-(IC3E-PB2-Pad20)") (class "Default")
      (node (ref "IC3") (pin "20") (pinfunction "PB2_20") (pintype "bidirectional"))
    )
    (net (code "81") (name "unconnected-(IC3E-PB3-Pad39)") (class "Default")
      (node (ref "IC3") (pin "39") (pinfunction "PB3_39") (pintype "bidirectional"))
    )
    (net (code "82") (name "unconnected-(IC3E-PB4-Pad40)") (class "Default")
      (node (ref "IC3") (pin "40") (pinfunction "PB4_40") (pintype "bidirectional"))
    )
    (net (code "83") (name "unconnected-(IC3E-PB5-Pad41)") (class "Default")
      (node (ref "IC3") (pin "41") (pinfunction "PB5_41") (pintype "bidirectional"))
    )
    (net (code "84") (name "unconnected-(IC3E-PB6-Pad42)") (class "Default")
      (node (ref "IC3") (pin "42") (pinfunction "PB6_42") (pintype "bidirectional"))
    )
    (net (code "85") (name "unconnected-(IC3E-PB7-Pad43)") (class "Default")
      (node (ref "IC3") (pin "43") (pinfunction "PB7_43") (pintype "bidirectional"))
    )
    (net (code "86") (name "unconnected-(IC3F-PC13-Pad2)") (class "Default")
      (node (ref "IC3") (pin "2") (pinfunction "PC13_2") (pintype "bidirectional"))
    )
    (net (code "87") (name "unconnected-(IC3F-PC14-Pad3)") (class "Default")
      (node (ref "IC3") (pin "3") (pinfunction "PC14_3") (pintype "bidirectional"))
    )
    (net (code "88") (name "unconnected-(IC3F-PC15-Pad4)") (class "Default")
      (node (ref "IC3") (pin "4") (pinfunction "PC15_4") (pintype "bidirectional"))
    )
    (net (code "89") (name "unconnected-(IC5-CMP-Pad5)") (class "Default")
      (node (ref "IC5") (pin "5") (pinfunction "CMP_5") (pintype "passive"))
    )
    (net (code "90") (name "unconnected-(IC5-ON-Pad1)") (class "Default")
      (node (ref "IC5") (pin "1") (pinfunction "ON_1") (pintype "passive"))
    )
    (net (code "91") (name "unconnected-(IC5-ON{slash}CMP-Pad8)") (class "Default")
      (node (ref "IC5") (pin "8") (pinfunction "ON/CMP_8") (pintype "passive"))
    )
    (net (code "92") (name "unconnected-(IC6-CMP-Pad5)") (class "Default")
      (node (ref "IC6") (pin "5") (pinfunction "CMP_5") (pintype "passive"))
    )
    (net (code "93") (name "unconnected-(IC6-ON-Pad1)") (class "Default")
      (node (ref "IC6") (pin "1") (pinfunction "ON_1") (pintype "passive"))
    )
    (net (code "94") (name "unconnected-(IC6-ON{slash}CMP-Pad8)") (class "Default")
      (node (ref "IC6") (pin "8") (pinfunction "ON/CMP_8") (pintype "passive"))
    )
    (net (code "95") (name "unconnected-(X3J-1-Pad9)") (class "Default")
      (node (ref "X3") (pin "9") (pinfunction "1_9") (pintype "passive"))
    )
    (net (code "96") (name "unconnected-(X4-Pad4)") (class "Default")
      (node (ref "X4") (pin "4") (pinfunction "4_4") (pintype "passive"))
    )
  )
)
